# R401X.net
KiCad netlist of a schematic drawn in EAGLE
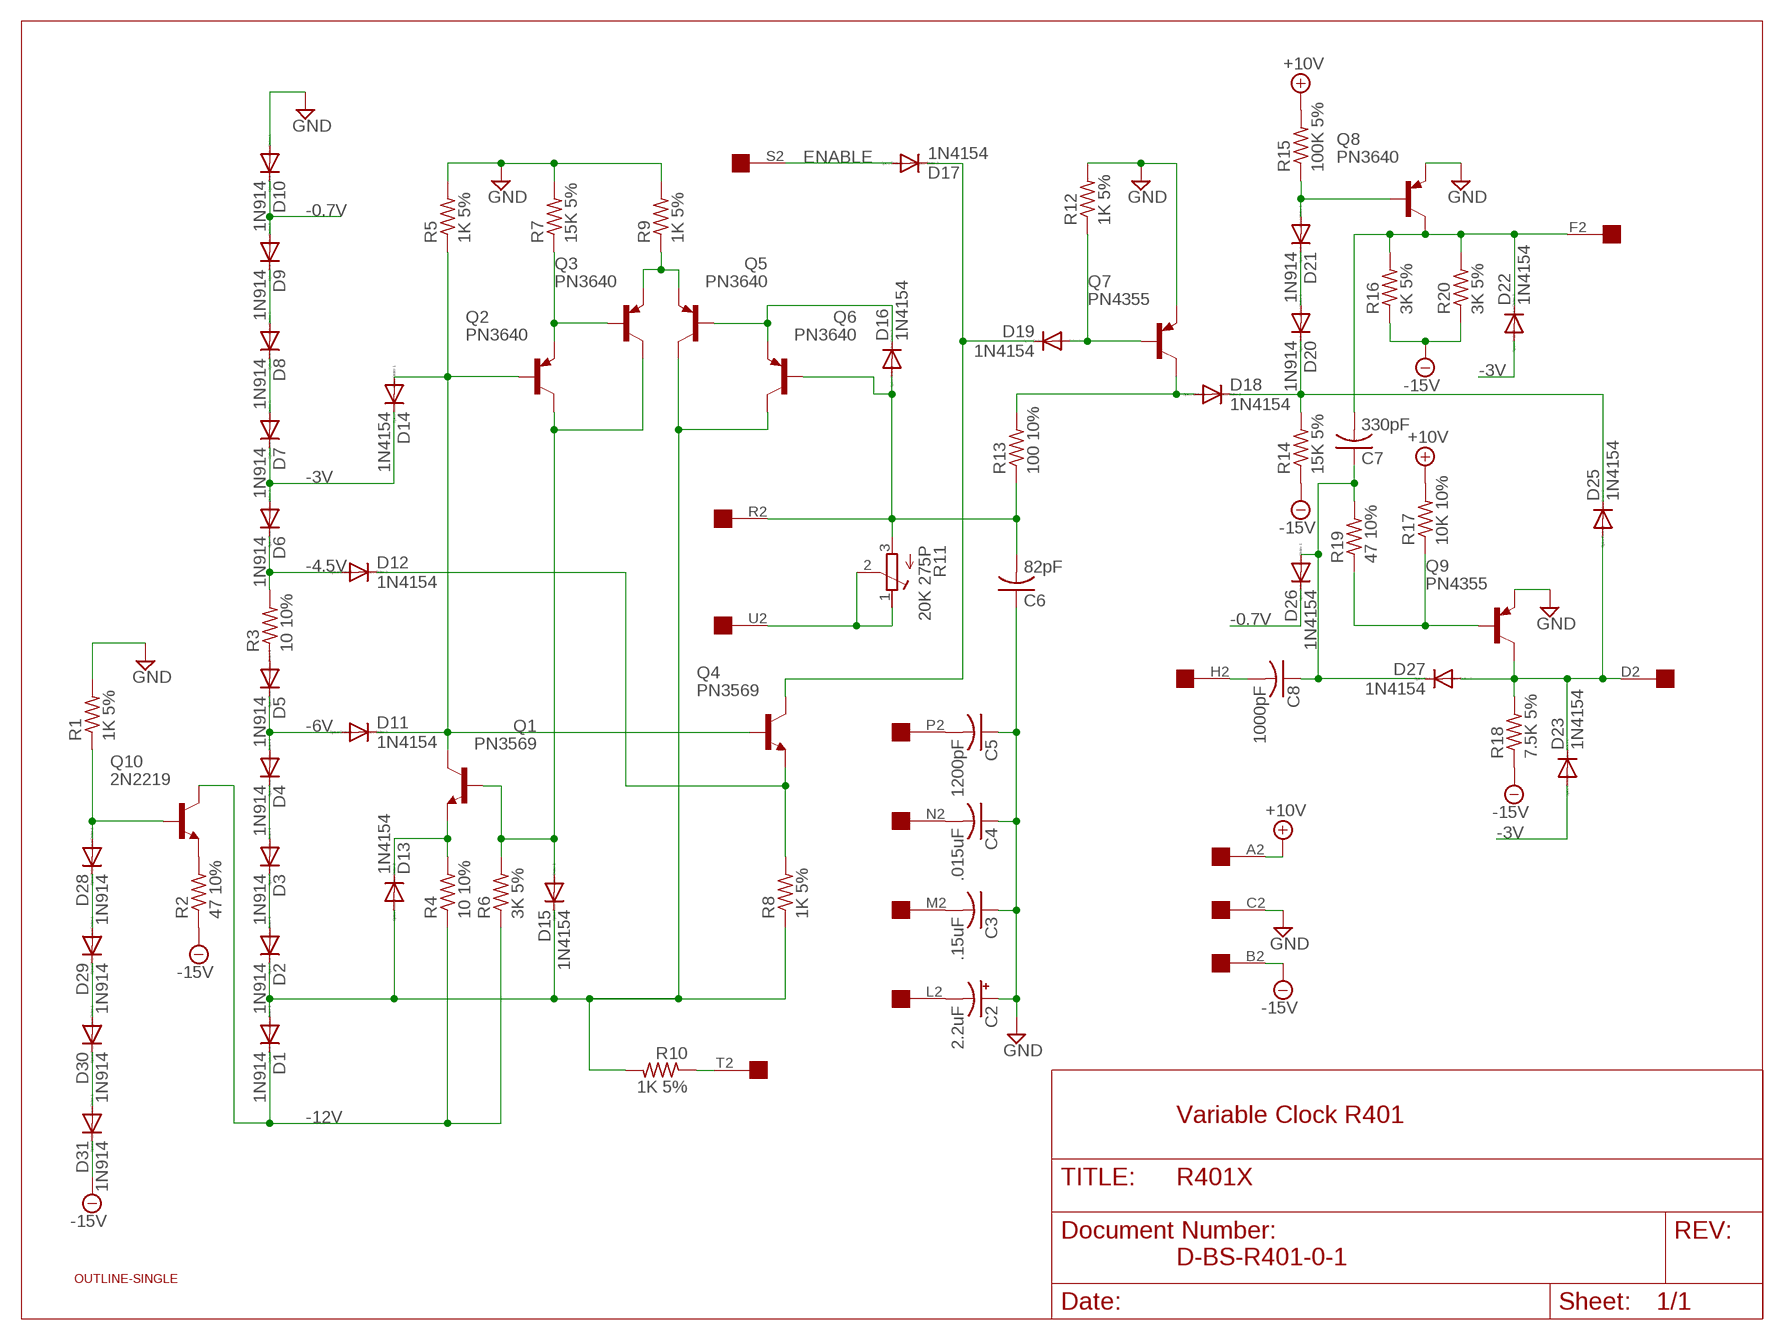
[diagram p0: schematic, sheet 1]

(export (version "E")
  (design (tool "Eeschema 10.0.6"))
  (components
    (comp (ref "C2")
      (value "2.2uF")
      (footprint "eagle-import:E12-4")
      (libsource (lib "eagle-import") (part "CPOL-USE12-4AXIAL"))
    )
    (comp (ref "C3")
      (value ".15uF")
      (footprint "eagle-import:C225-062X268")
      (libsource (lib "eagle-import") (part "C-US225-062X268"))
    )
    (comp (ref "C4")
      (value ".015uF")
      (footprint "eagle-import:C102-043X133")
      (libsource (lib "eagle-import") (part "C-US102-043X133"))
    )
    (comp (ref "C5")
      (value "1200pF")
      (footprint "eagle-import:C150-054X183")
      (libsource (lib "eagle-import") (part "C-US150-054X183"))
    )
    (comp (ref "C6")
      (value "82pF")
      (footprint "eagle-import:C102-043X133")
      (libsource (lib "eagle-import") (part "C-US102-043X133"))
    )
    (comp (ref "C7")
      (value "330pF")
      (footprint "eagle-import:C150-054X183")
      (libsource (lib "eagle-import") (part "C-US150-054X183"))
    )
    (comp (ref "C8")
      (value "1000pF")
      (footprint "eagle-import:C150-054X183")
      (libsource (lib "eagle-import") (part "C-US150-054X183"))
    )
    (comp (ref "D1")
      (value "1N914")
      (footprint "eagle-import:DO35-10")
      (libsource (lib "eagle-import") (part "1N4148DO35-10"))
    )
    (comp (ref "D2")
      (value "1N914")
      (footprint "eagle-import:DO35-10")
      (libsource (lib "eagle-import") (part "1N4148DO35-10"))
    )
    (comp (ref "D3")
      (value "1N914")
      (footprint "eagle-import:DO35-10")
      (libsource (lib "eagle-import") (part "1N4148DO35-10"))
    )
    (comp (ref "D4")
      (value "1N914")
      (footprint "eagle-import:DO35-10")
      (libsource (lib "eagle-import") (part "1N4148DO35-10"))
    )
    (comp (ref "D5")
      (value "1N914")
      (footprint "eagle-import:DO35-10")
      (libsource (lib "eagle-import") (part "1N4148DO35-10"))
    )
    (comp (ref "D6")
      (value "1N914")
      (footprint "eagle-import:DO35-10")
      (libsource (lib "eagle-import") (part "1N4148DO35-10"))
    )
    (comp (ref "D7")
      (value "1N914")
      (footprint "eagle-import:DO35-10")
      (libsource (lib "eagle-import") (part "1N4148DO35-10"))
    )
    (comp (ref "D8")
      (value "1N914")
      (footprint "eagle-import:DO35-10")
      (libsource (lib "eagle-import") (part "1N4148DO35-10"))
    )
    (comp (ref "D9")
      (value "1N914")
      (footprint "eagle-import:DO35-10")
      (libsource (lib "eagle-import") (part "1N4148DO35-10"))
    )
    (comp (ref "D10")
      (value "1N914")
      (footprint "eagle-import:DO35-10")
      (libsource (lib "eagle-import") (part "1N4148DO35-10"))
    )
    (comp (ref "D11")
      (value "1N4154")
      (footprint "eagle-import:DO35-10")
      (libsource (lib "eagle-import") (part "1N4148DO35-10"))
    )
    (comp (ref "D12")
      (value "1N4154")
      (footprint "eagle-import:DO35-10")
      (libsource (lib "eagle-import") (part "1N4148DO35-10"))
    )
    (comp (ref "D13")
      (value "1N4154")
      (footprint "eagle-import:DO35-10")
      (libsource (lib "eagle-import") (part "1N4148DO35-10"))
    )
    (comp (ref "D14")
      (value "1N4154")
      (footprint "eagle-import:DO35-10")
      (libsource (lib "eagle-import") (part "1N4148DO35-10"))
    )
    (comp (ref "D15")
      (value "1N4154")
      (footprint "eagle-import:DO35-10")
      (libsource (lib "eagle-import") (part "1N4148DO35-10"))
    )
    (comp (ref "D16")
      (value "1N4154")
      (footprint "eagle-import:DO35-10")
      (libsource (lib "eagle-import") (part "1N4148DO35-10"))
    )
    (comp (ref "D17")
      (value "1N4154")
      (footprint "eagle-import:DO35-10")
      (libsource (lib "eagle-import") (part "1N4148DO35-10"))
    )
    (comp (ref "D18")
      (value "1N4154")
      (footprint "eagle-import:DO35-10")
      (libsource (lib "eagle-import") (part "1N4148DO35-10"))
    )
    (comp (ref "D19")
      (value "1N4154")
      (footprint "eagle-import:DO35-10")
      (libsource (lib "eagle-import") (part "1N4148DO35-10"))
    )
    (comp (ref "D20")
      (value "1N914")
      (footprint "eagle-import:DO35-10")
      (libsource (lib "eagle-import") (part "1N4148DO35-10"))
    )
    (comp (ref "D21")
      (value "1N914")
      (footprint "eagle-import:DO35-10")
      (libsource (lib "eagle-import") (part "1N4148DO35-10"))
    )
    (comp (ref "D22")
      (value "1N4154")
      (footprint "eagle-import:DO35-10")
      (libsource (lib "eagle-import") (part "1N4148DO35-10"))
    )
    (comp (ref "D23")
      (value "1N4154")
      (footprint "eagle-import:DO35-10")
      (libsource (lib "eagle-import") (part "1N4148DO35-10"))
    )
    (comp (ref "D25")
      (value "1N4154")
      (footprint "eagle-import:DO35-10")
      (libsource (lib "eagle-import") (part "1N4148DO35-10"))
    )
    (comp (ref "D26")
      (value "1N4154")
      (footprint "eagle-import:DO35-10")
      (libsource (lib "eagle-import") (part "1N4148DO35-10"))
    )
    (comp (ref "D27")
      (value "1N4154")
      (footprint "eagle-import:DO35-10")
      (libsource (lib "eagle-import") (part "1N4148DO35-10"))
    )
    (comp (ref "D28")
      (value "1N914")
      (footprint "eagle-import:DO35-10")
      (libsource (lib "eagle-import") (part "1N4148DO35-10"))
    )
    (comp (ref "D29")
      (value "1N914")
      (footprint "eagle-import:DO35-10")
      (libsource (lib "eagle-import") (part "1N4148DO35-10"))
    )
    (comp (ref "D30")
      (value "1N914")
      (footprint "eagle-import:DO35-10")
      (libsource (lib "eagle-import") (part "1N4148DO35-10"))
    )
    (comp (ref "D31")
      (value "1N914")
      (footprint "eagle-import:DO35-10")
      (libsource (lib "eagle-import") (part "1N4148DO35-10"))
    )
    (comp (ref "Q1")
      (value "PN3569")
      (footprint "eagle-import:TO5")
      (libsource (lib "eagle-import") (part "2N2102"))
    )
    (comp (ref "Q2")
      (value "PN3640")
      (footprint "eagle-import:TO39")
      (libsource (lib "eagle-import") (part "2N2904"))
    )
    (comp (ref "Q3")
      (value "PN3640")
      (footprint "eagle-import:TO39")
      (libsource (lib "eagle-import") (part "2N2904"))
    )
    (comp (ref "Q4")
      (value "PN3569")
      (footprint "eagle-import:TO5")
      (libsource (lib "eagle-import") (part "2N2102"))
    )
    (comp (ref "Q5")
      (value "PN3640")
      (footprint "eagle-import:TO39")
      (libsource (lib "eagle-import") (part "2N2904"))
    )
    (comp (ref "Q6")
      (value "PN3640")
      (footprint "eagle-import:TO39")
      (libsource (lib "eagle-import") (part "2N2904"))
    )
    (comp (ref "Q7")
      (value "PN4355")
      (footprint "eagle-import:TO39")
      (libsource (lib "eagle-import") (part "2N2904"))
    )
    (comp (ref "Q8")
      (value "PN3640")
      (footprint "eagle-import:TO39")
      (libsource (lib "eagle-import") (part "2N2904"))
    )
    (comp (ref "Q9")
      (value "PN4355")
      (footprint "eagle-import:TO39")
      (libsource (lib "eagle-import") (part "2N2904"))
    )
    (comp (ref "Q10")
      (value "2N2219")
      (footprint "eagle-import:TO5")
      (libsource (lib "eagle-import") (part "2N2102"))
    )
    (comp (ref "R1")
      (value "1K 5%")
      (footprint "eagle-import:0207_10")
      (libsource (lib "eagle-import") (part "R-US_0207/10"))
    )
    (comp (ref "R2")
      (value "47 10%")
      (footprint "eagle-import:0207_10")
      (libsource (lib "eagle-import") (part "R-US_0207/10"))
    )
    (comp (ref "R3")
      (value "10 10%")
      (footprint "eagle-import:0207_10")
      (libsource (lib "eagle-import") (part "R-US_0207/10"))
    )
    (comp (ref "R4")
      (value "10 10%")
      (footprint "eagle-import:0207_10")
      (libsource (lib "eagle-import") (part "R-US_0207/10"))
    )
    (comp (ref "R5")
      (value "1K 5%")
      (footprint "eagle-import:0207_10")
      (libsource (lib "eagle-import") (part "R-US_0207/10"))
    )
    (comp (ref "R6")
      (value "3K 5%")
      (footprint "eagle-import:0207_10")
      (libsource (lib "eagle-import") (part "R-US_0207/10"))
    )
    (comp (ref "R7")
      (value "15K 5%")
      (footprint "eagle-import:0207_10")
      (libsource (lib "eagle-import") (part "R-US_0207/10"))
    )
    (comp (ref "R8")
      (value "1K 5%")
      (footprint "eagle-import:0207_10")
      (libsource (lib "eagle-import") (part "R-US_0207/10"))
    )
    (comp (ref "R9")
      (value "1K 5%")
      (footprint "eagle-import:0207_10")
      (libsource (lib "eagle-import") (part "R-US_0207/10"))
    )
    (comp (ref "R10")
      (value "1K 5%")
      (footprint "eagle-import:0207_10")
      (libsource (lib "eagle-import") (part "R-US_0207/10"))
    )
    (comp (ref "R11")
      (value "20K 275P")
      (footprint "eagle-import:3006Y")
      (libsource (lib "eagle-import") (part "275P"))
    )
    (comp (ref "R12")
      (value "1K 5%")
      (footprint "eagle-import:0207_10")
      (libsource (lib "eagle-import") (part "R-US_0207/10"))
    )
    (comp (ref "R13")
      (value "100 10%")
      (footprint "eagle-import:0207_10")
      (libsource (lib "eagle-import") (part "R-US_0207/10"))
    )
    (comp (ref "R14")
      (value "15K 5%")
      (footprint "eagle-import:0207_10")
      (libsource (lib "eagle-import") (part "R-US_0207/10"))
    )
    (comp (ref "R15")
      (value "100K 5%")
      (footprint "eagle-import:0207_10")
      (libsource (lib "eagle-import") (part "R-US_0207/10"))
    )
    (comp (ref "R16")
      (value "3K 5%")
      (footprint "eagle-import:0207_10")
      (libsource (lib "eagle-import") (part "R-US_0207/10"))
    )
    (comp (ref "R17")
      (value "10K 10%")
      (footprint "eagle-import:0207_10")
      (libsource (lib "eagle-import") (part "R-US_0207/10"))
    )
    (comp (ref "R18")
      (value "7.5K 5%")
      (footprint "eagle-import:0207_10")
      (libsource (lib "eagle-import") (part "R-US_0207/10"))
    )
    (comp (ref "R19")
      (value "47 10%")
      (footprint "eagle-import:0207_10")
      (libsource (lib "eagle-import") (part "R-US_0207/10"))
    )
    (comp (ref "R20")
      (value "3K 5%")
      (footprint "eagle-import:0207_10")
      (libsource (lib "eagle-import") (part "R-US_0207/10"))
    )
    (comp (ref "U$1")
      (value "OUTLINE-SINGLE")
      (footprint "eagle-import:SINGLE")
      (libsource (lib "eagle-import") (part "OUTLINE-SINGLE"))
    )
    (comp (ref "U$2")
      (value "EDGE-1")
      (footprint "eagle-import:EDGE-CON1")
      (libsource (lib "eagle-import") (part "EDGE-1"))
    )
  )
  (nets
    (net (code "1") (name "+10V") (class "Default")
      (node (ref "R15") (pin "2") (pinfunction "2_2") (pintype "passive"))
      (node (ref "R17") (pin "2") (pinfunction "2_2") (pintype "passive"))
      (node (ref "U$2") (pin "A2") (pinfunction "1_A2") (pintype "bidirectional"))
    )
    (net (code "2") (name "-15V") (class "Default")
      (node (ref "D31") (pin "C") (pinfunction "C_C") (pintype "passive"))
      (node (ref "R14") (pin "1") (pinfunction "1_1") (pintype "passive"))
      (node (ref "R16") (pin "1") (pinfunction "1_1") (pintype "passive"))
      (node (ref "R18") (pin "1") (pinfunction "1_1") (pintype "passive"))
      (node (ref "R2") (pin "1") (pinfunction "1_1") (pintype "passive"))
      (node (ref "R20") (pin "1") (pinfunction "1_1") (pintype "passive"))
      (node (ref "U$2") (pin "B2") (pinfunction "1_B2") (pintype "bidirectional"))
    )
    (net (code "3") (name "/-0.7V") (class "Default")
      (node (ref "D10") (pin "C") (pinfunction "C_C") (pintype "passive"))
      (node (ref "D26") (pin "C") (pinfunction "C_C") (pintype "passive"))
      (node (ref "D9") (pin "A") (pinfunction "A_A") (pintype "passive"))
    )
    (net (code "4") (name "/-3V") (class "Default")
      (node (ref "D14") (pin "C") (pinfunction "C_C") (pintype "passive"))
      (node (ref "D22") (pin "A") (pinfunction "A_A") (pintype "passive"))
      (node (ref "D23") (pin "A") (pinfunction "A_A") (pintype "passive"))
      (node (ref "D6") (pin "A") (pinfunction "A_A") (pintype "passive"))
      (node (ref "D7") (pin "C") (pinfunction "C_C") (pintype "passive"))
    )
    (net (code "5") (name "/-4.5V") (class "Default")
      (node (ref "D12") (pin "A") (pinfunction "A_A") (pintype "passive"))
      (node (ref "D6") (pin "C") (pinfunction "C_C") (pintype "passive"))
      (node (ref "R3") (pin "2") (pinfunction "2_2") (pintype "passive"))
    )
    (net (code "6") (name "/-6V") (class "Default")
      (node (ref "D11") (pin "A") (pinfunction "A_A") (pintype "passive"))
      (node (ref "D4") (pin "A") (pinfunction "A_A") (pintype "passive"))
      (node (ref "D5") (pin "C") (pinfunction "C_C") (pintype "passive"))
    )
    (net (code "7") (name "/-12V") (class "Default")
      (node (ref "D1") (pin "C") (pinfunction "C_C") (pintype "passive"))
      (node (ref "Q10") (pin "3") (pinfunction "C_3") (pintype "passive"))
      (node (ref "R4") (pin "1") (pinfunction "1_1") (pintype "passive"))
      (node (ref "R6") (pin "1") (pinfunction "1_1") (pintype "passive"))
    )
    (net (code "8") (name "/ENABLE") (class "Default")
      (node (ref "D17") (pin "A") (pinfunction "A_A") (pintype "passive"))
      (node (ref "U$2") (pin "S2") (pinfunction "1_S2") (pintype "bidirectional"))
    )
    (net (code "9") (name "GND") (class "Default")
      (node (ref "C2") (pin "+") (pinfunction "+_+") (pintype "passive"))
      (node (ref "C3") (pin "1") (pinfunction "1_1") (pintype "passive"))
      (node (ref "C4") (pin "1") (pinfunction "1_1") (pintype "passive"))
      (node (ref "C5") (pin "1") (pinfunction "1_1") (pintype "passive"))
      (node (ref "C6") (pin "1") (pinfunction "1_1") (pintype "passive"))
      (node (ref "D10") (pin "A") (pinfunction "A_A") (pintype "passive"))
      (node (ref "Q7") (pin "1") (pinfunction "E_1") (pintype "passive"))
      (node (ref "Q8") (pin "1") (pinfunction "E_1") (pintype "passive"))
      (node (ref "Q9") (pin "1") (pinfunction "E_1") (pintype "passive"))
      (node (ref "R1") (pin "2") (pinfunction "2_2") (pintype "passive"))
      (node (ref "R12") (pin "2") (pinfunction "2_2") (pintype "passive"))
      (node (ref "R5") (pin "2") (pinfunction "2_2") (pintype "passive"))
      (node (ref "R7") (pin "2") (pinfunction "2_2") (pintype "passive"))
      (node (ref "R9") (pin "2") (pinfunction "2_2") (pintype "passive"))
      (node (ref "U$2") (pin "C2") (pinfunction "1_C2") (pintype "bidirectional"))
    )
    (net (code "10") (name "Net-(C7-Pad1)") (class "Default")
      (node (ref "C7") (pin "1") (pinfunction "1_1") (pintype "passive"))
      (node (ref "C8") (pin "1") (pinfunction "1_1") (pintype "passive"))
      (node (ref "D26") (pin "A") (pinfunction "A_A") (pintype "passive"))
      (node (ref "D27") (pin "C") (pinfunction "C_C") (pintype "passive"))
      (node (ref "R19") (pin "2") (pinfunction "2_2") (pintype "passive"))
    )
    (net (code "11") (name "Net-(D2-PadA)") (class "Default")
      (node (ref "D2") (pin "A") (pinfunction "A_A") (pintype "passive"))
      (node (ref "D3") (pin "C") (pinfunction "C_C") (pintype "passive"))
    )
    (net (code "12") (name "Net-(D3-PadA)") (class "Default")
      (node (ref "D3") (pin "A") (pinfunction "A_A") (pintype "passive"))
      (node (ref "D4") (pin "C") (pinfunction "C_C") (pintype "passive"))
    )
    (net (code "13") (name "Net-(D5-PadA)") (class "Default")
      (node (ref "D5") (pin "A") (pinfunction "A_A") (pintype "passive"))
      (node (ref "R3") (pin "1") (pinfunction "1_1") (pintype "passive"))
    )
    (net (code "14") (name "Net-(D7-PadA)") (class "Default")
      (node (ref "D7") (pin "A") (pinfunction "A_A") (pintype "passive"))
      (node (ref "D8") (pin "C") (pinfunction "C_C") (pintype "passive"))
    )
    (net (code "15") (name "Net-(D8-PadA)") (class "Default")
      (node (ref "D8") (pin "A") (pinfunction "A_A") (pintype "passive"))
      (node (ref "D9") (pin "C") (pinfunction "C_C") (pintype "passive"))
    )
    (net (code "16") (name "Net-(D18-PadC)") (class "Default")
      (node (ref "D18") (pin "C") (pinfunction "C_C") (pintype "passive"))
      (node (ref "D20") (pin "C") (pinfunction "C_C") (pintype "passive"))
      (node (ref "D25") (pin "C") (pinfunction "C_C") (pintype "passive"))
      (node (ref "R14") (pin "2") (pinfunction "2_2") (pintype "passive"))
    )
    (net (code "17") (name "Net-(D20-PadA)") (class "Default")
      (node (ref "D20") (pin "A") (pinfunction "A_A") (pintype "passive"))
      (node (ref "D21") (pin "C") (pinfunction "C_C") (pintype "passive"))
    )
    (net (code "18") (name "Net-(D28-PadC)") (class "Default")
      (node (ref "D28") (pin "C") (pinfunction "C_C") (pintype "passive"))
      (node (ref "D29") (pin "A") (pinfunction "A_A") (pintype "passive"))
    )
    (net (code "19") (name "Net-(D29-PadC)") (class "Default")
      (node (ref "D29") (pin "C") (pinfunction "C_C") (pintype "passive"))
      (node (ref "D30") (pin "A") (pinfunction "A_A") (pintype "passive"))
    )
    (net (code "20") (name "Net-(D30-PadC)") (class "Default")
      (node (ref "D30") (pin "C") (pinfunction "C_C") (pintype "passive"))
      (node (ref "D31") (pin "A") (pinfunction "A_A") (pintype "passive"))
    )
    (net (code "21") (name "Net-(Q1-B)") (class "Default")
      (node (ref "D15") (pin "A") (pinfunction "A_A") (pintype "passive"))
      (node (ref "Q1") (pin "2") (pinfunction "B_2") (pintype "passive"))
      (node (ref "Q2") (pin "3") (pinfunction "C_3") (pintype "passive"))
      (node (ref "Q3") (pin "3") (pinfunction "C_3") (pintype "passive"))
      (node (ref "R6") (pin "2") (pinfunction "2_2") (pintype "passive"))
    )
    (net (code "22") (name "Net-(Q1-C)") (class "Default")
      (node (ref "D11") (pin "C") (pinfunction "C_C") (pintype "passive"))
      (node (ref "D14") (pin "A") (pinfunction "A_A") (pintype "passive"))
      (node (ref "Q1") (pin "3") (pinfunction "C_3") (pintype "passive"))
      (node (ref "Q2") (pin "2") (pinfunction "B_2") (pintype "passive"))
      (node (ref "Q4") (pin "2") (pinfunction "B_2") (pintype "passive"))
      (node (ref "R5") (pin "1") (pinfunction "1_1") (pintype "passive"))
    )
    (net (code "23") (name "Net-(Q1-E)") (class "Default")
      (node (ref "D13") (pin "C") (pinfunction "C_C") (pintype "passive"))
      (node (ref "Q1") (pin "1") (pinfunction "E_1") (pintype "passive"))
      (node (ref "R4") (pin "2") (pinfunction "2_2") (pintype "passive"))
    )
    (net (code "24") (name "Net-(Q2-E)") (class "Default")
      (node (ref "Q2") (pin "1") (pinfunction "E_1") (pintype "passive"))
      (node (ref "Q3") (pin "2") (pinfunction "B_2") (pintype "passive"))
      (node (ref "R7") (pin "1") (pinfunction "1_1") (pintype "passive"))
    )
    (net (code "25") (name "Net-(Q3-E)") (class "Default")
      (node (ref "Q3") (pin "1") (pinfunction "E_1") (pintype "passive"))
      (node (ref "Q5") (pin "1") (pinfunction "E_1") (pintype "passive"))
      (node (ref "R9") (pin "1") (pinfunction "1_1") (pintype "passive"))
    )
    (net (code "26") (name "Net-(Q4-C)") (class "Default")
      (node (ref "D17") (pin "C") (pinfunction "C_C") (pintype "passive"))
      (node (ref "D19") (pin "C") (pinfunction "C_C") (pintype "passive"))
      (node (ref "Q4") (pin "3") (pinfunction "C_3") (pintype "passive"))
    )
    (net (code "27") (name "Net-(Q4-E)") (class "Default")
      (node (ref "D12") (pin "C") (pinfunction "C_C") (pintype "passive"))
      (node (ref "Q4") (pin "1") (pinfunction "E_1") (pintype "passive"))
      (node (ref "R8") (pin "2") (pinfunction "2_2") (pintype "passive"))
    )
    (net (code "28") (name "Net-(Q5-B)") (class "Default")
      (node (ref "D16") (pin "C") (pinfunction "C_C") (pintype "passive"))
      (node (ref "Q5") (pin "2") (pinfunction "B_2") (pintype "passive"))
      (node (ref "Q6") (pin "1") (pinfunction "E_1") (pintype "passive"))
    )
    (net (code "29") (name "Net-(Q5-C)") (class "Default")
      (node (ref "D1") (pin "A") (pinfunction "A_A") (pintype "passive"))
      (node (ref "D13") (pin "A") (pinfunction "A_A") (pintype "passive"))
      (node (ref "D15") (pin "C") (pinfunction "C_C") (pintype "passive"))
      (node (ref "D2") (pin "C") (pinfunction "C_C") (pintype "passive"))
      (node (ref "Q5") (pin "3") (pinfunction "C_3") (pintype "passive"))
      (node (ref "Q6") (pin "3") (pinfunction "C_3") (pintype "passive"))
      (node (ref "R10") (pin "2") (pinfunction "2_2") (pintype "passive"))
      (node (ref "R8") (pin "1") (pinfunction "1_1") (pintype "passive"))
    )
    (net (code "30") (name "Net-(Q6-B)") (class "Default")
      (node (ref "C6") (pin "2") (pinfunction "2_2") (pintype "passive"))
      (node (ref "D16") (pin "A") (pinfunction "A_A") (pintype "passive"))
      (node (ref "Q6") (pin "2") (pinfunction "B_2") (pintype "passive"))
      (node (ref "R11") (pin "3") (pinfunction "E_3") (pintype "passive"))
      (node (ref "R13") (pin "1") (pinfunction "1_1") (pintype "passive"))
      (node (ref "U$2") (pin "R2") (pinfunction "1_R2") (pintype "bidirectional"))
    )
    (net (code "31") (name "Net-(Q7-B)") (class "Default")
      (node (ref "D19") (pin "A") (pinfunction "A_A") (pintype "passive"))
      (node (ref "Q7") (pin "2") (pinfunction "B_2") (pintype "passive"))
      (node (ref "R12") (pin "1") (pinfunction "1_1") (pintype "passive"))
    )
    (net (code "32") (name "Net-(Q7-C)") (class "Default")
      (node (ref "D18") (pin "A") (pinfunction "A_A") (pintype "passive"))
      (node (ref "Q7") (pin "3") (pinfunction "C_3") (pintype "passive"))
      (node (ref "R13") (pin "2") (pinfunction "2_2") (pintype "passive"))
    )
    (net (code "33") (name "Net-(Q8-B)") (class "Default")
      (node (ref "D21") (pin "A") (pinfunction "A_A") (pintype "passive"))
      (node (ref "Q8") (pin "2") (pinfunction "B_2") (pintype "passive"))
      (node (ref "R15") (pin "1") (pinfunction "1_1") (pintype "passive"))
    )
    (net (code "34") (name "Net-(Q8-C)") (class "Default")
      (node (ref "C7") (pin "2") (pinfunction "2_2") (pintype "passive"))
      (node (ref "D22") (pin "C") (pinfunction "C_C") (pintype "passive"))
      (node (ref "Q8") (pin "3") (pinfunction "C_3") (pintype "passive"))
      (node (ref "R16") (pin "2") (pinfunction "2_2") (pintype "passive"))
      (node (ref "R20") (pin "2") (pinfunction "2_2") (pintype "passive"))
      (node (ref "U$2") (pin "F2") (pinfunction "1_F2") (pintype "bidirectional"))
    )
    (net (code "35") (name "Net-(Q9-B)") (class "Default")
      (node (ref "Q9") (pin "2") (pinfunction "B_2") (pintype "passive"))
      (node (ref "R17") (pin "1") (pinfunction "1_1") (pintype "passive"))
      (node (ref "R19") (pin "1") (pinfunction "1_1") (pintype "passive"))
    )
    (net (code "36") (name "Net-(Q9-C)") (class "Default")
      (node (ref "D23") (pin "C") (pinfunction "C_C") (pintype "passive"))
      (node (ref "D25") (pin "A") (pinfunction "A_A") (pintype "passive"))
      (node (ref "D27") (pin "A") (pinfunction "A_A") (pintype "passive"))
      (node (ref "Q9") (pin "3") (pinfunction "C_3") (pintype "passive"))
      (node (ref "R18") (pin "2") (pinfunction "2_2") (pintype "passive"))
      (node (ref "U$2") (pin "D2") (pinfunction "1_D2") (pintype "bidirectional"))
    )
    (net (code "37") (name "Net-(Q10-B)") (class "Default")
      (node (ref "D28") (pin "A") (pinfunction "A_A") (pintype "passive"))
      (node (ref "Q10") (pin "2") (pinfunction "B_2") (pintype "passive"))
      (node (ref "R1") (pin "1") (pinfunction "1_1") (pintype "passive"))
    )
    (net (code "38") (name "Net-(Q10-E)") (class "Default")
      (node (ref "Q10") (pin "1") (pinfunction "E_1") (pintype "passive"))
      (node (ref "R2") (pin "2") (pinfunction "2_2") (pintype "passive"))
    )
    (net (code "39") (name "Net-(R11-A)") (class "Default")
      (node (ref "R11") (pin "1") (pinfunction "A_1") (pintype "passive"))
      (node (ref "R11") (pin "2") (pinfunction "S_2") (pintype "passive"))
      (node (ref "U$2") (pin "U2") (pinfunction "1_U2") (pintype "bidirectional"))
    )
    (net (code "40") (name "Net-(U$2G-1)") (class "Default")
      (node (ref "C8") (pin "2") (pinfunction "2_2") (pintype "passive"))
      (node (ref "U$2") (pin "H2") (pinfunction "1_H2") (pintype "bidirectional"))
    )
    (net (code "41") (name "Net-(U$2J-1)") (class "Default")
      (node (ref "C2") (pin "-") (pinfunction "-_-") (pintype "passive"))
      (node (ref "U$2") (pin "L2") (pinfunction "1_L2") (pintype "bidirectional"))
    )
    (net (code "42") (name "Net-(U$2K-1)") (class "Default")
      (node (ref "C3") (pin "2") (pinfunction "2_2") (pintype "passive"))
      (node (ref "U$2") (pin "M2") (pinfunction "1_M2") (pintype "bidirectional"))
    )
    (net (code "43") (name "Net-(U$2L-1)") (class "Default")
      (node (ref "C4") (pin "2") (pinfunction "2_2") (pintype "passive"))
      (node (ref "U$2") (pin "N2") (pinfunction "1_N2") (pintype "bidirectional"))
    )
    (net (code "44") (name "Net-(U$2M-1)") (class "Default")
      (node (ref "C5") (pin "2") (pinfunction "2_2") (pintype "passive"))
      (node (ref "U$2") (pin "P2") (pinfunction "1_P2") (pintype "bidirectional"))
    )
    (net (code "45") (name "Net-(U$2P-1)") (class "Default")
      (node (ref "R10") (pin "1") (pinfunction "1_1") (pintype "passive"))
      (node (ref "U$2") (pin "T2") (pinfunction "1_T2") (pintype "bidirectional"))
    )
  )
)
